# passe-bande_5kHz.net
KiCad netlist of a schematic drawn in Altium Designer
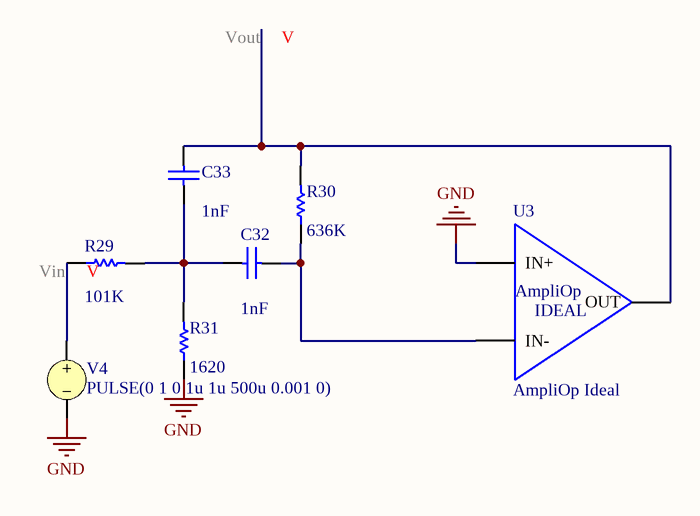
[diagram p0: passe-bande 5kHz.SchDoc]

(export (version "E")
  (design (tool "Eeschema 10.0.6"))
  (components
    (comp (ref "C32")
      (value "1nF")
      (footprint "RAD-0.3")
      (description "Capacitor")
      (fields (field (name "Comment") "Cap") (field (name "PUBLISHER") "Altium Limited"))
      (libsource (lib "Miscellaneous Devices") (part "Cap"))
    )
    (comp (ref "C33")
      (value "1nF")
      (footprint "RAD-0.3")
      (description "Capacitor")
      (fields (field (name "Comment") "Cap") (field (name "PUBLISHER") "Altium Limited"))
      (libsource (lib "Miscellaneous Devices") (part "Cap"))
    )
    (comp (ref "R29")
      (value "101K")
      (footprint "AXIAL-0.3")
      (description "Resistor")
      (fields (field (name "Comment") "Res1") (field (name "PUBLISHER") "Altium Limited"))
      (libsource (lib "Miscellaneous Devices") (part "Res1"))
    )
    (comp (ref "R30")
      (value "636K")
      (footprint "AXIAL-0.3")
      (description "Resistor")
      (fields (field (name "Comment") "Res1") (field (name "PUBLISHER") "Altium Limited"))
      (libsource (lib "Miscellaneous Devices") (part "Res1"))
    )
    (comp (ref "R31")
      (value "1620")
      (footprint "AXIAL-0.3")
      (description "Resistor")
      (fields (field (name "Comment") "Res1") (field (name "PUBLISHER") "Altium Limited"))
      (libsource (lib "Miscellaneous Devices") (part "Res1"))
    )
    (comp (ref "U3") (value "AmpliOp Ideal") (libsource (lib "Librarie_S2") (part "AmpliOp_ideal")))
    (comp (ref "V4")
      (value "PULSE(0 1 0 1u 1u 500u 0.001 0)")
      (description "Voltage Source")
      (fields (field (name "PUBLISHER") "Altium Limited"))
      (libsource (lib "Simulation Sources") (part "VSRC"))
    )
  )
  (nets
    (net (code "1") (name "GND") (class "Default")
      (node (ref "R31") (pin "1") (pinfunction "1_1") (pintype "passive"))
      (node (ref "U3") (pin "1") (pinfunction "IN+_1") (pintype "passive"))
      (node (ref "V4") (pin "2") (pinfunction "2_2") (pintype "passive"))
    )
    (net (code "2") (name "Net-(C32-Pad1)") (class "Default")
      (node (ref "C32") (pin "1") (pinfunction "1_1") (pintype "passive"))
      (node (ref "C33") (pin "1") (pinfunction "1_1") (pintype "passive"))
      (node (ref "R29") (pin "2") (pinfunction "2_2") (pintype "passive"))
      (node (ref "R31") (pin "2") (pinfunction "2_2") (pintype "passive"))
    )
    (net (code "3") (name "Net-(R29-Pad1)") (class "Default")
      (node (ref "R29") (pin "1") (pinfunction "1_1") (pintype "passive"))
      (node (ref "V4") (pin "1") (pinfunction "1_1") (pintype "passive"))
    )
    (net (code "4") (name "Net-(U3-IN-)") (class "Default")
      (node (ref "C32") (pin "2") (pinfunction "2_2") (pintype "passive"))
      (node (ref "R30") (pin "1") (pinfunction "1_1") (pintype "passive"))
      (node (ref "U3") (pin "2") (pinfunction "IN-_2") (pintype "passive"))
    )
    (net (code "5") (name "Net-(U3-OUT)") (class "Default")
      (node (ref "C33") (pin "2") (pinfunction "2_2") (pintype "passive"))
      (node (ref "R30") (pin "2") (pinfunction "2_2") (pintype "passive"))
      (node (ref "U3") (pin "3") (pinfunction "OUT_3") (pintype "passive"))
    )
  )
)
